# laser-simple.net
KiCad netlist of a schematic drawn in EAGLE
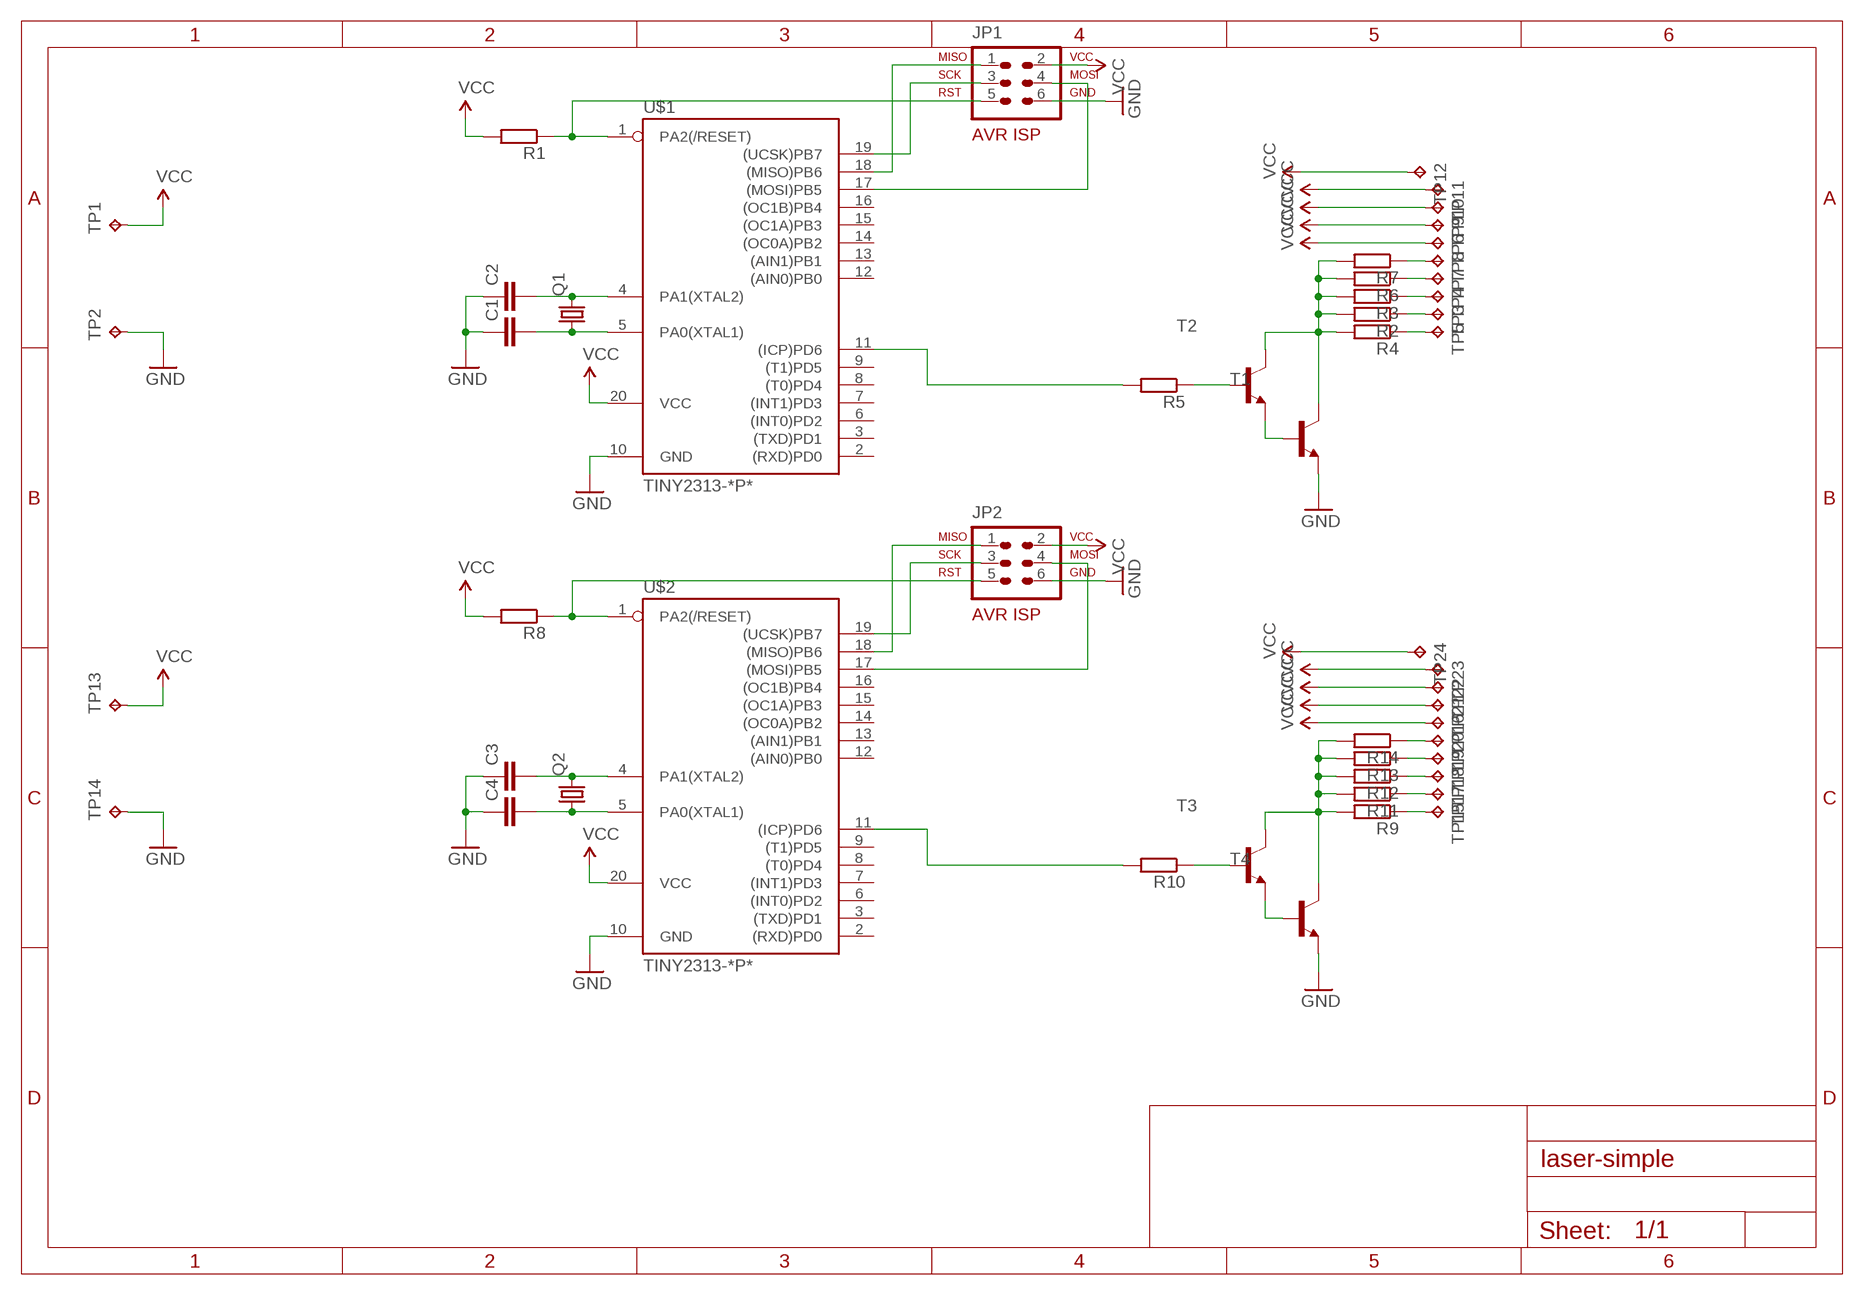
[diagram p0: schematic, sheet 1]

(export (version "E")
  (design (tool "Eeschema 10.0.6"))
  (components
    (comp (ref "C1")
      (value "C-EU050-024X044")
      (footprint "eagle-import:C050-024X044")
      (libsource (lib "eagle-import") (part "C-EU050-024X044"))
    )
    (comp (ref "C2")
      (value "C-EU050-024X044")
      (footprint "eagle-import:C050-024X044")
      (libsource (lib "eagle-import") (part "C-EU050-024X044"))
    )
    (comp (ref "C3")
      (value "C-EU050-024X044")
      (footprint "eagle-import:C050-024X044")
      (libsource (lib "eagle-import") (part "C-EU050-024X044"))
    )
    (comp (ref "C4")
      (value "C-EU050-024X044")
      (footprint "eagle-import:C050-024X044")
      (libsource (lib "eagle-import") (part "C-EU050-024X044"))
    )
    (comp (ref "JP1")
      (value "AVR-ISP-6VERT")
      (footprint "eagle-import:AVR-ISP-6")
      (libsource (lib "eagle-import") (part "AVR-ISP-6VERT"))
    )
    (comp (ref "JP2")
      (value "AVR-ISP-6VERT")
      (footprint "eagle-import:AVR-ISP-6")
      (libsource (lib "eagle-import") (part "AVR-ISP-6VERT"))
    )
    (comp (ref "Q1")
      (value "CRYSTALHC49U-V")
      (footprint "eagle-import:HC49U-V")
      (libsource (lib "eagle-import") (part "CRYSTALHC49U-V"))
    )
    (comp (ref "Q2")
      (value "CRYSTALHC49U-V")
      (footprint "eagle-import:HC49U-V")
      (libsource (lib "eagle-import") (part "CRYSTALHC49U-V"))
    )
    (comp (ref "R1")
      (value "R-EU_0207/10")
      (footprint "eagle-import:0207_10")
      (libsource (lib "eagle-import") (part "R-EU_0207/10"))
    )
    (comp (ref "R2")
      (value "R-EU_0207/10")
      (footprint "eagle-import:0207_10")
      (libsource (lib "eagle-import") (part "R-EU_0207/10"))
    )
    (comp (ref "R3")
      (value "R-EU_0207/10")
      (footprint "eagle-import:0207_10")
      (libsource (lib "eagle-import") (part "R-EU_0207/10"))
    )
    (comp (ref "R4")
      (value "R-EU_0207/10")
      (footprint "eagle-import:0207_10")
      (libsource (lib "eagle-import") (part "R-EU_0207/10"))
    )
    (comp (ref "R5")
      (value "R-EU_0207/10")
      (footprint "eagle-import:0207_10")
      (libsource (lib "eagle-import") (part "R-EU_0207/10"))
    )
    (comp (ref "R6")
      (value "R-EU_0207/10")
      (footprint "eagle-import:0207_10")
      (libsource (lib "eagle-import") (part "R-EU_0207/10"))
    )
    (comp (ref "R7")
      (value "R-EU_0207/10")
      (footprint "eagle-import:0207_10")
      (libsource (lib "eagle-import") (part "R-EU_0207/10"))
    )
    (comp (ref "R8")
      (value "R-EU_0207/10")
      (footprint "eagle-import:0207_10")
      (libsource (lib "eagle-import") (part "R-EU_0207/10"))
    )
    (comp (ref "R9")
      (value "R-EU_0207/10")
      (footprint "eagle-import:0207_10")
      (libsource (lib "eagle-import") (part "R-EU_0207/10"))
    )
    (comp (ref "R10")
      (value "R-EU_0207/10")
      (footprint "eagle-import:0207_10")
      (libsource (lib "eagle-import") (part "R-EU_0207/10"))
    )
    (comp (ref "R11")
      (value "R-EU_0207/10")
      (footprint "eagle-import:0207_10")
      (libsource (lib "eagle-import") (part "R-EU_0207/10"))
    )
    (comp (ref "R12")
      (value "R-EU_0207/10")
      (footprint "eagle-import:0207_10")
      (libsource (lib "eagle-import") (part "R-EU_0207/10"))
    )
    (comp (ref "R13")
      (value "R-EU_0207/10")
      (footprint "eagle-import:0207_10")
      (libsource (lib "eagle-import") (part "R-EU_0207/10"))
    )
    (comp (ref "R14")
      (value "R-EU_0207/10")
      (footprint "eagle-import:0207_10")
      (libsource (lib "eagle-import") (part "R-EU_0207/10"))
    )
    (comp (ref "T1")
      (value "2N1711-NPN-TO39-EBC")
      (footprint "eagle-import:TO39")
      (libsource (lib "eagle-import") (part "-NPN-TO39-EBC2N1711"))
    )
    (comp (ref "T2")
      (value "2N1711-NPN-TO39-EBC")
      (footprint "eagle-import:TO39")
      (libsource (lib "eagle-import") (part "-NPN-TO39-EBC2N1711"))
    )
    (comp (ref "T3")
      (value "2N1711-NPN-TO39-EBC")
      (footprint "eagle-import:TO39")
      (libsource (lib "eagle-import") (part "-NPN-TO39-EBC2N1711"))
    )
    (comp (ref "T4")
      (value "2N1711-NPN-TO39-EBC")
      (footprint "eagle-import:TO39")
      (libsource (lib "eagle-import") (part "-NPN-TO39-EBC2N1711"))
    )
    (comp (ref "TP1")
      (value "TPPAD1-13Y")
      (footprint "eagle-import:P1-13Y")
      (libsource (lib "eagle-import") (part "TPPAD1-13Y"))
    )
    (comp (ref "TP2")
      (value "TPPAD1-13Y")
      (footprint "eagle-import:P1-13Y")
      (libsource (lib "eagle-import") (part "TPPAD1-13Y"))
    )
    (comp (ref "TP3")
      (value "TPPAD1-13Y")
      (footprint "eagle-import:P1-13Y")
      (libsource (lib "eagle-import") (part "TPPAD1-13Y"))
    )
    (comp (ref "TP4")
      (value "TPPAD1-13Y")
      (footprint "eagle-import:P1-13Y")
      (libsource (lib "eagle-import") (part "TPPAD1-13Y"))
    )
    (comp (ref "TP5")
      (value "TPPAD1-13Y")
      (footprint "eagle-import:P1-13Y")
      (libsource (lib "eagle-import") (part "TPPAD1-13Y"))
    )
    (comp (ref "TP6")
      (value "TPPAD1-13Y")
      (footprint "eagle-import:P1-13Y")
      (libsource (lib "eagle-import") (part "TPPAD1-13Y"))
    )
    (comp (ref "TP7")
      (value "TPPAD1-13Y")
      (footprint "eagle-import:P1-13Y")
      (libsource (lib "eagle-import") (part "TPPAD1-13Y"))
    )
    (comp (ref "TP8")
      (value "TPPAD1-13Y")
      (footprint "eagle-import:P1-13Y")
      (libsource (lib "eagle-import") (part "TPPAD1-13Y"))
    )
    (comp (ref "TP9")
      (value "TPPAD1-13Y")
      (footprint "eagle-import:P1-13Y")
      (libsource (lib "eagle-import") (part "TPPAD1-13Y"))
    )
    (comp (ref "TP10")
      (value "TPPAD1-13Y")
      (footprint "eagle-import:P1-13Y")
      (libsource (lib "eagle-import") (part "TPPAD1-13Y"))
    )
    (comp (ref "TP11")
      (value "TPPAD1-13Y")
      (footprint "eagle-import:P1-13Y")
      (libsource (lib "eagle-import") (part "TPPAD1-13Y"))
    )
    (comp (ref "TP12")
      (value "TPPAD1-13Y")
      (footprint "eagle-import:P1-13Y")
      (libsource (lib "eagle-import") (part "TPPAD1-13Y"))
    )
    (comp (ref "TP13")
      (value "TPPAD1-13Y")
      (footprint "eagle-import:P1-13Y")
      (libsource (lib "eagle-import") (part "TPPAD1-13Y"))
    )
    (comp (ref "TP14")
      (value "TPPAD1-13Y")
      (footprint "eagle-import:P1-13Y")
      (libsource (lib "eagle-import") (part "TPPAD1-13Y"))
    )
    (comp (ref "TP15")
      (value "TPPAD1-13Y")
      (footprint "eagle-import:P1-13Y")
      (libsource (lib "eagle-import") (part "TPPAD1-13Y"))
    )
    (comp (ref "TP16")
      (value "TPPAD1-13Y")
      (footprint "eagle-import:P1-13Y")
      (libsource (lib "eagle-import") (part "TPPAD1-13Y"))
    )
    (comp (ref "TP17")
      (value "TPPAD1-13Y")
      (footprint "eagle-import:P1-13Y")
      (libsource (lib "eagle-import") (part "TPPAD1-13Y"))
    )
    (comp (ref "TP18")
      (value "TPPAD1-13Y")
      (footprint "eagle-import:P1-13Y")
      (libsource (lib "eagle-import") (part "TPPAD1-13Y"))
    )
    (comp (ref "TP19")
      (value "TPPAD1-13Y")
      (footprint "eagle-import:P1-13Y")
      (libsource (lib "eagle-import") (part "TPPAD1-13Y"))
    )
    (comp (ref "TP20")
      (value "TPPAD1-13Y")
      (footprint "eagle-import:P1-13Y")
      (libsource (lib "eagle-import") (part "TPPAD1-13Y"))
    )
    (comp (ref "TP21")
      (value "TPPAD1-13Y")
      (footprint "eagle-import:P1-13Y")
      (libsource (lib "eagle-import") (part "TPPAD1-13Y"))
    )
    (comp (ref "TP22")
      (value "TPPAD1-13Y")
      (footprint "eagle-import:P1-13Y")
      (libsource (lib "eagle-import") (part "TPPAD1-13Y"))
    )
    (comp (ref "TP23")
      (value "TPPAD1-13Y")
      (footprint "eagle-import:P1-13Y")
      (libsource (lib "eagle-import") (part "TPPAD1-13Y"))
    )
    (comp (ref "TP24")
      (value "TPPAD1-13Y")
      (footprint "eagle-import:P1-13Y")
      (libsource (lib "eagle-import") (part "TPPAD1-13Y"))
    )
    (comp (ref "U$1")
      (value "TINY2313-*P*")
      (footprint "eagle-import:DIL20")
      (libsource (lib "eagle-import") (part "TINY2313-P"))
    )
    (comp (ref "U$2")
      (value "TINY2313-*P*")
      (footprint "eagle-import:DIL20")
      (libsource (lib "eagle-import") (part "TINY2313-P"))
    )
  )
  (nets
    (net (code "1") (name "GND") (class "Default")
      (node (ref "C1") (pin "1") (pinfunction "1_1") (pintype "passive"))
      (node (ref "C2") (pin "1") (pinfunction "1_1") (pintype "passive"))
      (node (ref "C3") (pin "1") (pinfunction "1_1") (pintype "passive"))
      (node (ref "C4") (pin "1") (pinfunction "1_1") (pintype "passive"))
      (node (ref "JP1") (pin "6") (pinfunction "6_6") (pintype "passive"))
      (node (ref "JP2") (pin "6") (pinfunction "6_6") (pintype "passive"))
      (node (ref "T1") (pin "1") (pinfunction "E_1") (pintype "passive"))
      (node (ref "T4") (pin "1") (pinfunction "E_1") (pintype "passive"))
      (node (ref "TP14") (pin "TP") (pinfunction "TP_TP") (pintype "input"))
      (node (ref "TP2") (pin "TP") (pinfunction "TP_TP") (pintype "input"))
      (node (ref "U$1") (pin "10") (pinfunction "GND_10") (pintype "power_in"))
      (node (ref "U$2") (pin "10") (pinfunction "GND_10") (pintype "power_in"))
    )
    (net (code "2") (name "Net-(R2-Pad1)") (class "Default")
      (node (ref "R2") (pin "1") (pinfunction "1_1") (pintype "passive"))
      (node (ref "TP3") (pin "TP") (pinfunction "TP_TP") (pintype "input"))
    )
    (net (code "3") (name "Net-(R3-Pad1)") (class "Default")
      (node (ref "R3") (pin "1") (pinfunction "1_1") (pintype "passive"))
      (node (ref "TP4") (pin "TP") (pinfunction "TP_TP") (pintype "input"))
    )
    (net (code "4") (name "Net-(R4-Pad1)") (class "Default")
      (node (ref "R4") (pin "1") (pinfunction "1_1") (pintype "passive"))
      (node (ref "TP5") (pin "TP") (pinfunction "TP_TP") (pintype "input"))
    )
    (net (code "5") (name "Net-(R6-Pad1)") (class "Default")
      (node (ref "R6") (pin "1") (pinfunction "1_1") (pintype "passive"))
      (node (ref "TP7") (pin "TP") (pinfunction "TP_TP") (pintype "input"))
    )
    (net (code "6") (name "Net-(R7-Pad1)") (class "Default")
      (node (ref "R7") (pin "1") (pinfunction "1_1") (pintype "passive"))
      (node (ref "TP8") (pin "TP") (pinfunction "TP_TP") (pintype "input"))
    )
    (net (code "7") (name "Net-(R9-Pad1)") (class "Default")
      (node (ref "R9") (pin "1") (pinfunction "1_1") (pintype "passive"))
      (node (ref "TP15") (pin "TP") (pinfunction "TP_TP") (pintype "input"))
    )
    (net (code "8") (name "Net-(R11-Pad1)") (class "Default")
      (node (ref "R11") (pin "1") (pinfunction "1_1") (pintype "passive"))
      (node (ref "TP17") (pin "TP") (pinfunction "TP_TP") (pintype "input"))
    )
    (net (code "9") (name "Net-(R12-Pad1)") (class "Default")
      (node (ref "R12") (pin "1") (pinfunction "1_1") (pintype "passive"))
      (node (ref "TP18") (pin "TP") (pinfunction "TP_TP") (pintype "input"))
    )
    (net (code "10") (name "Net-(R13-Pad1)") (class "Default")
      (node (ref "R13") (pin "1") (pinfunction "1_1") (pintype "passive"))
      (node (ref "TP19") (pin "TP") (pinfunction "TP_TP") (pintype "input"))
    )
    (net (code "11") (name "Net-(R14-Pad1)") (class "Default")
      (node (ref "R14") (pin "1") (pinfunction "1_1") (pintype "passive"))
      (node (ref "TP20") (pin "TP") (pinfunction "TP_TP") (pintype "input"))
    )
    (net (code "12") (name "Net-(T1-B)") (class "Default")
      (node (ref "T1") (pin "2") (pinfunction "B_2") (pintype "passive"))
      (node (ref "T2") (pin "1") (pinfunction "E_1") (pintype "passive"))
    )
    (net (code "13") (name "Net-(T1-C)") (class "Default")
      (node (ref "R2") (pin "2") (pinfunction "2_2") (pintype "passive"))
      (node (ref "R3") (pin "2") (pinfunction "2_2") (pintype "passive"))
      (node (ref "R4") (pin "2") (pinfunction "2_2") (pintype "passive"))
      (node (ref "R6") (pin "2") (pinfunction "2_2") (pintype "passive"))
      (node (ref "R7") (pin "2") (pinfunction "2_2") (pintype "passive"))
      (node (ref "T1") (pin "3") (pinfunction "C_3") (pintype "passive"))
      (node (ref "T2") (pin "3") (pinfunction "C_3") (pintype "passive"))
    )
    (net (code "14") (name "Net-(T2-B)") (class "Default")
      (node (ref "R5") (pin "1") (pinfunction "1_1") (pintype "passive"))
      (node (ref "T2") (pin "2") (pinfunction "B_2") (pintype "passive"))
    )
    (net (code "15") (name "Net-(T3-B)") (class "Default")
      (node (ref "R10") (pin "1") (pinfunction "1_1") (pintype "passive"))
      (node (ref "T3") (pin "2") (pinfunction "B_2") (pintype "passive"))
    )
    (net (code "16") (name "Net-(T3-C)") (class "Default")
      (node (ref "R11") (pin "2") (pinfunction "2_2") (pintype "passive"))
      (node (ref "R12") (pin "2") (pinfunction "2_2") (pintype "passive"))
      (node (ref "R13") (pin "2") (pinfunction "2_2") (pintype "passive"))
      (node (ref "R14") (pin "2") (pinfunction "2_2") (pintype "passive"))
      (node (ref "R9") (pin "2") (pinfunction "2_2") (pintype "passive"))
      (node (ref "T3") (pin "3") (pinfunction "C_3") (pintype "passive"))
      (node (ref "T4") (pin "3") (pinfunction "C_3") (pintype "passive"))
    )
    (net (code "17") (name "Net-(T3-E)") (class "Default")
      (node (ref "T3") (pin "1") (pinfunction "E_1") (pintype "passive"))
      (node (ref "T4") (pin "2") (pinfunction "B_2") (pintype "passive"))
    )
    (net (code "18") (name "Net-(U$1-(ICP)PD6)") (class "Default")
      (node (ref "R5") (pin "2") (pinfunction "2_2") (pintype "passive"))
      (node (ref "U$1") (pin "11") (pinfunction "(ICP)PD6_11") (pintype "bidirectional"))
    )
    (net (code "19") (name "Net-(U$1-(MISO)PB6)") (class "Default")
      (node (ref "JP1") (pin "1") (pinfunction "1_1") (pintype "passive"))
      (node (ref "U$1") (pin "18") (pinfunction "(MISO)PB6_18") (pintype "bidirectional"))
    )
    (net (code "20") (name "Net-(U$1-(MOSI)PB5)") (class "Default")
      (node (ref "JP1") (pin "4") (pinfunction "4_4") (pintype "passive"))
      (node (ref "U$1") (pin "17") (pinfunction "(MOSI)PB5_17") (pintype "bidirectional"))
    )
    (net (code "21") (name "Net-(U$1-(UCSK)PB7)") (class "Default")
      (node (ref "JP1") (pin "3") (pinfunction "3_3") (pintype "passive"))
      (node (ref "U$1") (pin "19") (pinfunction "(UCSK)PB7_19") (pintype "bidirectional"))
    )
    (net (code "22") (name "Net-(U$1-PA0(XTAL1))") (class "Default")
      (node (ref "C1") (pin "2") (pinfunction "2_2") (pintype "passive"))
      (node (ref "Q1") (pin "1") (pinfunction "1_1") (pintype "passive"))
      (node (ref "U$1") (pin "5") (pinfunction "PA0(XTAL1)_5") (pintype "bidirectional"))
    )
    (net (code "23") (name "Net-(U$1-PA1(XTAL2))") (class "Default")
      (node (ref "C2") (pin "2") (pinfunction "2_2") (pintype "passive"))
      (node (ref "Q1") (pin "2") (pinfunction "2_2") (pintype "passive"))
      (node (ref "U$1") (pin "4") (pinfunction "PA1(XTAL2)_4") (pintype "bidirectional"))
    )
    (net (code "24") (name "Net-(U$1-PA2({slash}RESET))") (class "Default")
      (node (ref "JP1") (pin "5") (pinfunction "5_5") (pintype "passive"))
      (node (ref "R1") (pin "1") (pinfunction "1_1") (pintype "passive"))
      (node (ref "U$1") (pin "1") (pinfunction "PA2(/RESET)_1") (pintype "input"))
    )
    (net (code "25") (name "Net-(U$2-(ICP)PD6)") (class "Default")
      (node (ref "R10") (pin "2") (pinfunction "2_2") (pintype "passive"))
      (node (ref "U$2") (pin "11") (pinfunction "(ICP)PD6_11") (pintype "bidirectional"))
    )
    (net (code "26") (name "Net-(U$2-(MISO)PB6)") (class "Default")
      (node (ref "JP2") (pin "1") (pinfunction "1_1") (pintype "passive"))
      (node (ref "U$2") (pin "18") (pinfunction "(MISO)PB6_18") (pintype "bidirectional"))
    )
    (net (code "27") (name "Net-(U$2-(MOSI)PB5)") (class "Default")
      (node (ref "JP2") (pin "4") (pinfunction "4_4") (pintype "passive"))
      (node (ref "U$2") (pin "17") (pinfunction "(MOSI)PB5_17") (pintype "bidirectional"))
    )
    (net (code "28") (name "Net-(U$2-(UCSK)PB7)") (class "Default")
      (node (ref "JP2") (pin "3") (pinfunction "3_3") (pintype "passive"))
      (node (ref "U$2") (pin "19") (pinfunction "(UCSK)PB7_19") (pintype "bidirectional"))
    )
    (net (code "29") (name "Net-(U$2-PA0(XTAL1))") (class "Default")
      (node (ref "C4") (pin "2") (pinfunction "2_2") (pintype "passive"))
      (node (ref "Q2") (pin "1") (pinfunction "1_1") (pintype "passive"))
      (node (ref "U$2") (pin "5") (pinfunction "PA0(XTAL1)_5") (pintype "bidirectional"))
    )
    (net (code "30") (name "Net-(U$2-PA1(XTAL2))") (class "Default")
      (node (ref "C3") (pin "2") (pinfunction "2_2") (pintype "passive"))
      (node (ref "Q2") (pin "2") (pinfunction "2_2") (pintype "passive"))
      (node (ref "U$2") (pin "4") (pinfunction "PA1(XTAL2)_4") (pintype "bidirectional"))
    )
    (net (code "31") (name "Net-(U$2-PA2({slash}RESET))") (class "Default")
      (node (ref "JP2") (pin "5") (pinfunction "5_5") (pintype "passive"))
      (node (ref "R8") (pin "1") (pinfunction "1_1") (pintype "passive"))
      (node (ref "U$2") (pin "1") (pinfunction "PA2(/RESET)_1") (pintype "input"))
    )
    (net (code "32") (name "VCC") (class "Default")
      (node (ref "JP1") (pin "2") (pinfunction "2_2") (pintype "passive"))
      (node (ref "JP2") (pin "2") (pinfunction "2_2") (pintype "passive"))
      (node (ref "R1") (pin "2") (pinfunction "2_2") (pintype "passive"))
      (node (ref "R8") (pin "2") (pinfunction "2_2") (pintype "passive"))
      (node (ref "TP1") (pin "TP") (pinfunction "TP_TP") (pintype "input"))
      (node (ref "TP10") (pin "TP") (pinfunction "TP_TP") (pintype "input"))
      (node (ref "TP11") (pin "TP") (pinfunction "TP_TP") (pintype "input"))
      (node (ref "TP12") (pin "TP") (pinfunction "TP_TP") (pintype "input"))
      (node (ref "TP13") (pin "TP") (pinfunction "TP_TP") (pintype "input"))
      (node (ref "TP16") (pin "TP") (pinfunction "TP_TP") (pintype "input"))
      (node (ref "TP21") (pin "TP") (pinfunction "TP_TP") (pintype "input"))
      (node (ref "TP22") (pin "TP") (pinfunction "TP_TP") (pintype "input"))
      (node (ref "TP23") (pin "TP") (pinfunction "TP_TP") (pintype "input"))
      (node (ref "TP24") (pin "TP") (pinfunction "TP_TP") (pintype "input"))
      (node (ref "TP6") (pin "TP") (pinfunction "TP_TP") (pintype "input"))
      (node (ref "TP9") (pin "TP") (pinfunction "TP_TP") (pintype "input"))
      (node (ref "U$1") (pin "20") (pinfunction "VCC_20") (pintype "power_in"))
      (node (ref "U$2") (pin "20") (pinfunction "VCC_20") (pintype "power_in"))
    )
    (net (code "33") (name "unconnected-(U$1-(AIN0)PB0-Pad12)") (class "Default")
      (node (ref "U$1") (pin "12") (pinfunction "(AIN0)PB0_12") (pintype "bidirectional"))
    )
    (net (code "34") (name "unconnected-(U$1-(AIN1)PB1-Pad13)") (class "Default")
      (node (ref "U$1") (pin "13") (pinfunction "(AIN1)PB1_13") (pintype "bidirectional"))
    )
    (net (code "35") (name "unconnected-(U$1-(INT0)PD2-Pad6)") (class "Default")
      (node (ref "U$1") (pin "6") (pinfunction "(INT0)PD2_6") (pintype "bidirectional"))
    )
    (net (code "36") (name "unconnected-(U$1-(INT1)PD3-Pad7)") (class "Default")
      (node (ref "U$1") (pin "7") (pinfunction "(INT1)PD3_7") (pintype "bidirectional"))
    )
    (net (code "37") (name "unconnected-(U$1-(OC0A)PB2-Pad14)") (class "Default")
      (node (ref "U$1") (pin "14") (pinfunction "(OC0A)PB2_14") (pintype "bidirectional"))
    )
    (net (code "38") (name "unconnected-(U$1-(OC1A)PB3-Pad15)") (class "Default")
      (node (ref "U$1") (pin "15") (pinfunction "(OC1A)PB3_15") (pintype "bidirectional"))
    )
    (net (code "39") (name "unconnected-(U$1-(OC1B)PB4-Pad16)") (class "Default")
      (node (ref "U$1") (pin "16") (pinfunction "(OC1B)PB4_16") (pintype "bidirectional"))
    )
    (net (code "40") (name "unconnected-(U$1-(RXD)PD0-Pad2)") (class "Default")
      (node (ref "U$1") (pin "2") (pinfunction "(RXD)PD0_2") (pintype "bidirectional"))
    )
    (net (code "41") (name "unconnected-(U$1-(T0)PD4-Pad8)") (class "Default")
      (node (ref "U$1") (pin "8") (pinfunction "(T0)PD4_8") (pintype "bidirectional"))
    )
    (net (code "42") (name "unconnected-(U$1-(T1)PD5-Pad9)") (class "Default")
      (node (ref "U$1") (pin "9") (pinfunction "(T1)PD5_9") (pintype "bidirectional"))
    )
    (net (code "43") (name "unconnected-(U$1-(TXD)PD1-Pad3)") (class "Default")
      (node (ref "U$1") (pin "3") (pinfunction "(TXD)PD1_3") (pintype "bidirectional"))
    )
    (net (code "44") (name "unconnected-(U$2-(AIN0)PB0-Pad12)") (class "Default")
      (node (ref "U$2") (pin "12") (pinfunction "(AIN0)PB0_12") (pintype "bidirectional"))
    )
    (net (code "45") (name "unconnected-(U$2-(AIN1)PB1-Pad13)") (class "Default")
      (node (ref "U$2") (pin "13") (pinfunction "(AIN1)PB1_13") (pintype "bidirectional"))
    )
    (net (code "46") (name "unconnected-(U$2-(INT0)PD2-Pad6)") (class "Default")
      (node (ref "U$2") (pin "6") (pinfunction "(INT0)PD2_6") (pintype "bidirectional"))
    )
    (net (code "47") (name "unconnected-(U$2-(INT1)PD3-Pad7)") (class "Default")
      (node (ref "U$2") (pin "7") (pinfunction "(INT1)PD3_7") (pintype "bidirectional"))
    )
    (net (code "48") (name "unconnected-(U$2-(OC0A)PB2-Pad14)") (class "Default")
      (node (ref "U$2") (pin "14") (pinfunction "(OC0A)PB2_14") (pintype "bidirectional"))
    )
    (net (code "49") (name "unconnected-(U$2-(OC1A)PB3-Pad15)") (class "Default")
      (node (ref "U$2") (pin "15") (pinfunction "(OC1A)PB3_15") (pintype "bidirectional"))
    )
    (net (code "50") (name "unconnected-(U$2-(OC1B)PB4-Pad16)") (class "Default")
      (node (ref "U$2") (pin "16") (pinfunction "(OC1B)PB4_16") (pintype "bidirectional"))
    )
    (net (code "51") (name "unconnected-(U$2-(RXD)PD0-Pad2)") (class "Default")
      (node (ref "U$2") (pin "2") (pinfunction "(RXD)PD0_2") (pintype "bidirectional"))
    )
    (net (code "52") (name "unconnected-(U$2-(T0)PD4-Pad8)") (class "Default")
      (node (ref "U$2") (pin "8") (pinfunction "(T0)PD4_8") (pintype "bidirectional"))
    )
    (net (code "53") (name "unconnected-(U$2-(T1)PD5-Pad9)") (class "Default")
      (node (ref "U$2") (pin "9") (pinfunction "(T1)PD5_9") (pintype "bidirectional"))
    )
    (net (code "54") (name "unconnected-(U$2-(TXD)PD1-Pad3)") (class "Default")
      (node (ref "U$2") (pin "3") (pinfunction "(TXD)PD1_3") (pintype "bidirectional"))
    )
  )
)
